# aufsatz_v2_3_usb.net
KiCad netlist of a schematic drawn in EAGLE
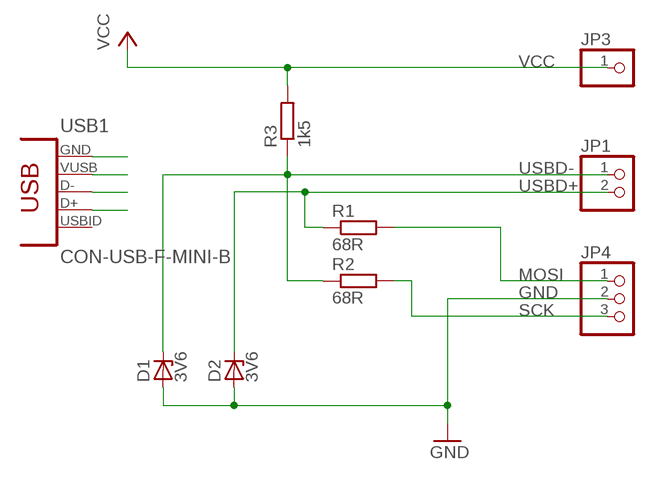
[diagram p0: schematic, sheet 1]

(export (version "E")
  (design (tool "Eeschema 10.0.6"))
  (components
    (comp (ref "D1")
      (value "3V6")
      (footprint "eagle-import:SOD80C")
      (libsource (lib "eagle-import") (part "ZENER-DIODESOD80C"))
    )
    (comp (ref "D2")
      (value "3V6")
      (footprint "eagle-import:SOD80C")
      (libsource (lib "eagle-import") (part "ZENER-DIODESOD80C"))
    )
    (comp (ref "JP1")
      (value "PINHD-1X2")
      (footprint "eagle-import:1X02")
      (libsource (lib "eagle-import") (part "PINHD-1X2"))
    )
    (comp (ref "JP3")
      (value "PINHD-1X1")
      (footprint "eagle-import:1X01")
      (libsource (lib "eagle-import") (part "PINHD-1X1"))
    )
    (comp (ref "JP4")
      (value "PINHD-1X3")
      (footprint "eagle-import:1X03")
      (libsource (lib "eagle-import") (part "PINHD-1X3"))
    )
    (comp (ref "R1")
      (value "68R")
      (footprint "eagle-import:R0805")
      (libsource (lib "eagle-import") (part "R-EU_R0805"))
    )
    (comp (ref "R2")
      (value "68R")
      (footprint "eagle-import:R0805")
      (libsource (lib "eagle-import") (part "R-EU_R0805"))
    )
    (comp (ref "R3")
      (value "1k5")
      (footprint "eagle-import:R0805")
      (libsource (lib "eagle-import") (part "R-EU_R0805"))
    )
    (comp (ref "USB1")
      (value "CON-USB-F-MINI-B")
      (footprint "eagle-import:CONN_USB_MINI-B")
      (libsource (lib "eagle-import") (part "CON-USB-F-MINI-B"))
    )
  )
  (nets
    (net (code "1") (name "/MOSI") (class "Default")
      (node (ref "JP4") (pin "1") (pinfunction "1_1") (pintype "passive"))
      (node (ref "R1") (pin "2") (pinfunction "2_2") (pintype "passive"))
    )
    (net (code "2") (name "/SCK") (class "Default")
      (node (ref "JP4") (pin "3") (pinfunction "3_3") (pintype "passive"))
      (node (ref "R2") (pin "2") (pinfunction "2_2") (pintype "passive"))
    )
    (net (code "3") (name "/USBD+") (class "Default")
      (node (ref "D2") (pin "C") (pinfunction "C_C") (pintype "passive"))
      (node (ref "JP1") (pin "2") (pinfunction "2_2") (pintype "passive"))
      (node (ref "R1") (pin "1") (pinfunction "1_1") (pintype "passive"))
      (node (ref "USB1") (pin "D+") (pinfunction "D+_D+") (pintype "bidirectional"))
    )
    (net (code "4") (name "/USBD-") (class "Default")
      (node (ref "D1") (pin "C") (pinfunction "C_C") (pintype "passive"))
      (node (ref "JP1") (pin "1") (pinfunction "1_1") (pintype "passive"))
      (node (ref "R2") (pin "1") (pinfunction "1_1") (pintype "passive"))
      (node (ref "R3") (pin "1") (pinfunction "1_1") (pintype "passive"))
      (node (ref "USB1") (pin "D-") (pinfunction "D-_D-") (pintype "bidirectional"))
    )
    (net (code "5") (name "GND") (class "Default")
      (node (ref "D1") (pin "A") (pinfunction "A_A") (pintype "passive"))
      (node (ref "D2") (pin "A") (pinfunction "A_A") (pintype "passive"))
      (node (ref "JP4") (pin "2") (pinfunction "2_2") (pintype "passive"))
      (node (ref "USB1") (pin "GND") (pinfunction "GND_GND") (pintype "bidirectional"))
    )
    (net (code "6") (name "VCC") (class "Default")
      (node (ref "JP3") (pin "1") (pinfunction "1_1") (pintype "passive"))
      (node (ref "R3") (pin "2") (pinfunction "2_2") (pintype "passive"))
      (node (ref "USB1") (pin "VUSB") (pinfunction "VUSB_VUSB") (pintype "bidirectional"))
    )
    (net (code "7") (name "unconnected-(USB1B-USBID-PadID)") (class "Default")
      (node (ref "USB1") (pin "ID") (pinfunction "USBID_ID") (pintype "bidirectional"))
    )
  )
)
